# MS5611.net
KiCad netlist of a schematic drawn in EAGLE
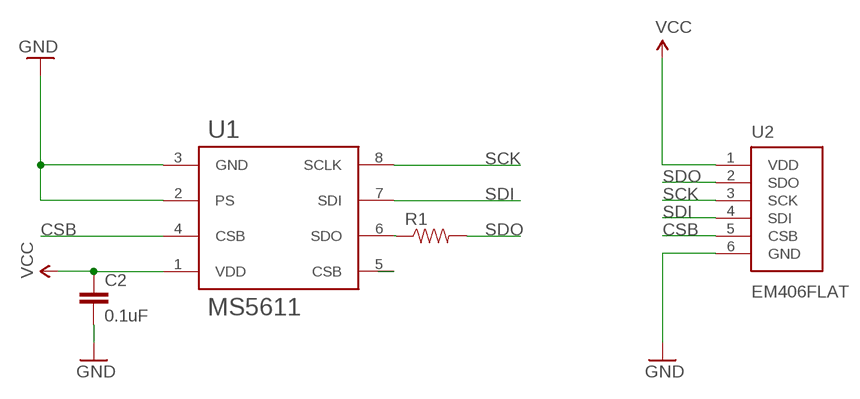
[diagram p0: schematic, sheet 1]

(export (version "E")
  (design (tool "Eeschema 10.0.6"))
  (components
    (comp (ref "C2")
      (value "0.1uF")
      (footprint "eagle-import:0603-CAP")
      (libsource (lib "eagle-import") (part "CAP0603-CAP"))
    )
    (comp (ref "R1")
      (value "RESISTOR0603-RES")
      (footprint "eagle-import:0603-RES")
      (libsource (lib "eagle-import") (part "RESISTOR0603-RES"))
    )
    (comp (ref "U1")
      (value "MS5611")
      (footprint "eagle-import:QFN-8")
      (libsource (lib "eagle-import") (part "MS5611"))
    )
    (comp (ref "U2")
      (value "EM406FLAT")
      (footprint "eagle-import:EM406-FLAT")
      (libsource (lib "eagle-import") (part "EM406FLAT"))
    )
  )
  (nets
    (net (code "1") (name "/CSB") (class "Default")
      (node (ref "U1") (pin "4") (pinfunction "CSB_4") (pintype "power_in"))
      (node (ref "U2") (pin "5") (pinfunction "CSB_5") (pintype "bidirectional"))
    )
    (net (code "2") (name "/SCK") (class "Default")
      (node (ref "U1") (pin "8") (pinfunction "SCLK_8") (pintype "bidirectional"))
      (node (ref "U2") (pin "3") (pinfunction "SCK_3") (pintype "bidirectional"))
    )
    (net (code "3") (name "/SDI") (class "Default")
      (node (ref "U1") (pin "7") (pinfunction "SDI_7") (pintype "bidirectional"))
      (node (ref "U2") (pin "4") (pinfunction "SDI_4") (pintype "bidirectional"))
    )
    (net (code "4") (name "/SDO") (class "Default")
      (node (ref "R1") (pin "2") (pinfunction "2_2") (pintype "passive"))
      (node (ref "U2") (pin "2") (pinfunction "SDO_2") (pintype "bidirectional"))
    )
    (net (code "5") (name "GND") (class "Default")
      (node (ref "C2") (pin "2") (pinfunction "2_2") (pintype "passive"))
      (node (ref "U1") (pin "2") (pinfunction "PS_2") (pintype "power_in"))
      (node (ref "U1") (pin "3") (pinfunction "GND_3") (pintype "power_in"))
      (node (ref "U2") (pin "6") (pinfunction "GND_6") (pintype "bidirectional"))
    )
    (net (code "6") (name "Net-(U1-SDO)") (class "Default")
      (node (ref "R1") (pin "1") (pinfunction "1_1") (pintype "passive"))
      (node (ref "U1") (pin "6") (pinfunction "SDO_6") (pintype "bidirectional"))
    )
    (net (code "7") (name "VCC") (class "Default")
      (node (ref "C2") (pin "1") (pinfunction "1_1") (pintype "passive"))
      (node (ref "U1") (pin "1") (pinfunction "VDD_1") (pintype "power_in"))
      (node (ref "U2") (pin "1") (pinfunction "VDD_1") (pintype "bidirectional"))
    )
    (net (code "8") (name "unconnected-(U1-CSB-Pad5)") (class "Default")
      (node (ref "U1") (pin "5") (pinfunction "CSB_5") (pintype "power_in"))
    )
  )
)
